# thermistor_board.net
KiCad netlist of a schematic drawn in EAGLE
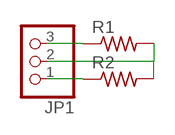
[diagram p0: schematic, sheet 1]

(export (version "E")
  (design (tool "Eeschema 10.0.6"))
  (components
    (comp (ref "JP1")
      (value "PINHD-1X3")
      (footprint "eagle-import:1X03")
      (libsource (lib "eagle-import") (part "PINHD-1X3"))
    )
    (comp (ref "R1")
      (value "RES-US1206")
      (footprint "eagle-import:R1206")
      (libsource (lib "eagle-import") (part "RES-US1206"))
    )
    (comp (ref "R2")
      (value "RES-US1206")
      (footprint "eagle-import:R1206")
      (libsource (lib "eagle-import") (part "RES-US1206"))
    )
  )
  (nets
    (net (code "1") (name "Net-(JP1-Pad1)") (class "Default")
      (node (ref "JP1") (pin "1") (pinfunction "1_1") (pintype "passive"))
      (node (ref "R2") (pin "1") (pinfunction "1_1") (pintype "passive"))
    )
    (net (code "2") (name "Net-(JP1-Pad2)") (class "Default")
      (node (ref "JP1") (pin "2") (pinfunction "2_2") (pintype "passive"))
      (node (ref "R1") (pin "2") (pinfunction "2_2") (pintype "passive"))
      (node (ref "R2") (pin "2") (pinfunction "2_2") (pintype "passive"))
    )
    (net (code "3") (name "Net-(JP1-Pad3)") (class "Default")
      (node (ref "JP1") (pin "3") (pinfunction "3_3") (pintype "passive"))
      (node (ref "R1") (pin "1") (pinfunction "1_1") (pintype "passive"))
    )
  )
)
